# Debugger_Circuit.net
KiCad netlist of a schematic drawn in Altium Designer
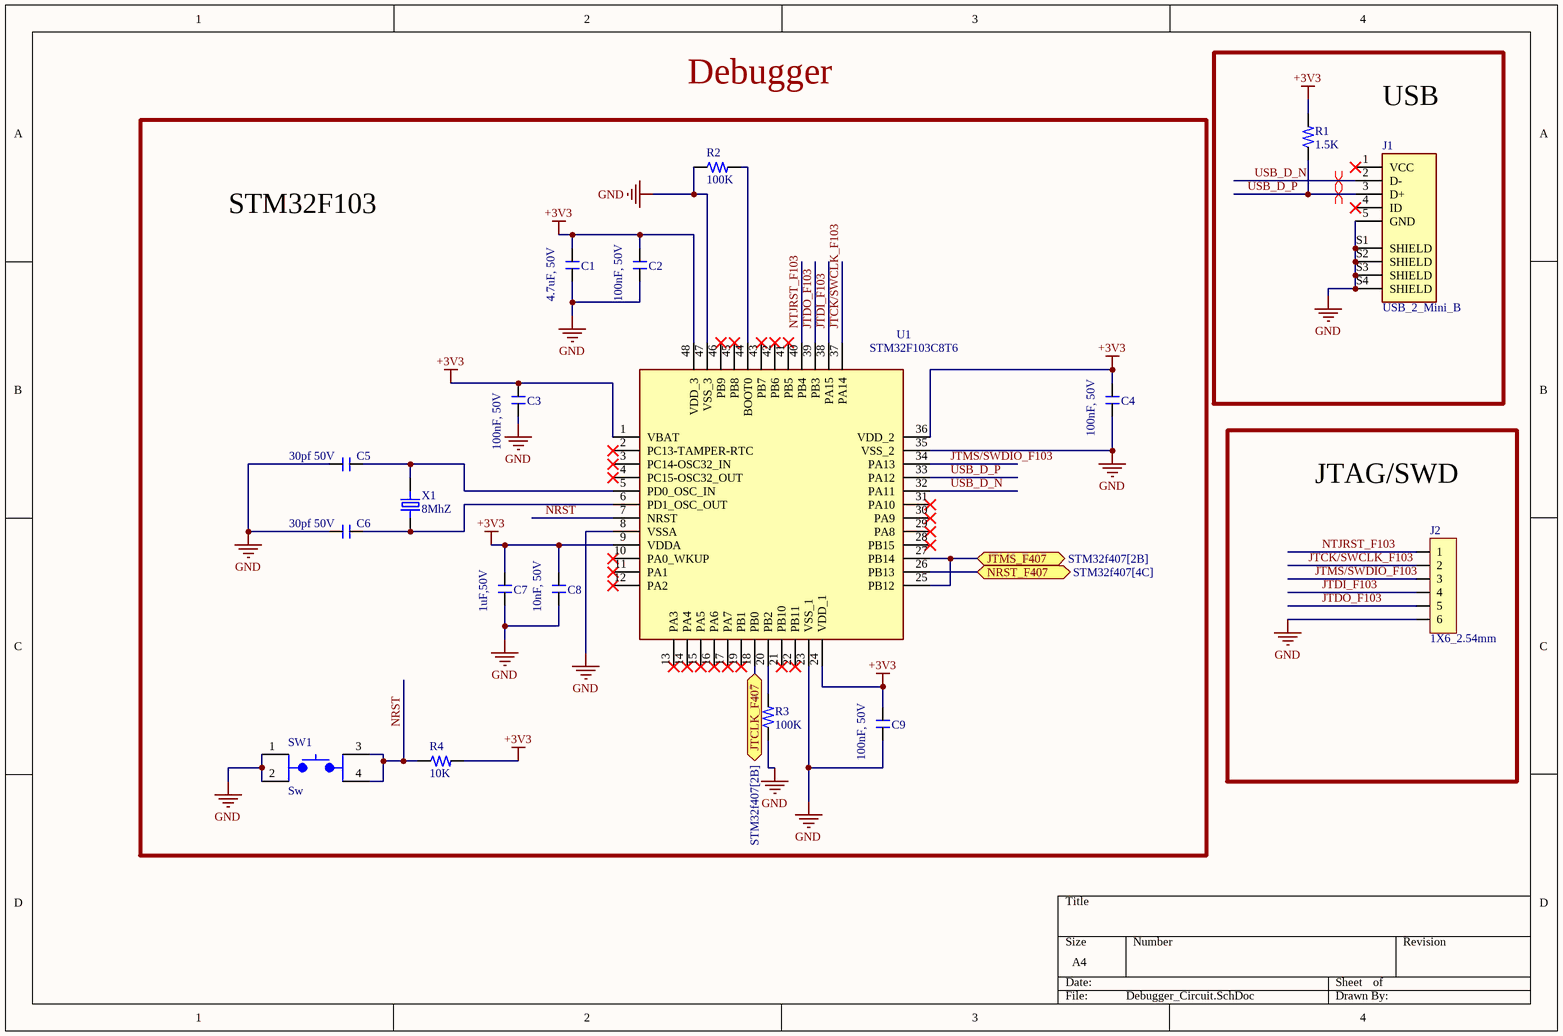
[diagram p0: Debugger_Circuit.SchDoc]

(export (version "E")
  (design (tool "Eeschema 10.0.6"))
  (components
    (comp (ref "C1")
      (value "4.7uF, 50V")
      (footprint "Capacitor_0805")
      (description "Multilayer Ceramic Capacitor, 4.7 uF, 50 V, ï¿½ 10%, X5R, 0805 [2012 Metric]")
      (fields
        (field (name "MANUFACTURER") "Murata")
        (field (name "MANUFACTURER PART NUMBER") "GRM21BR61H475KE51L")
      )
      (libsource (lib "Schematics_Library_Hanif") (part "Cap_4.7uF_0805"))
    )
    (comp (ref "C2")
      (value "100nF, 50V")
      (footprint "Capacitor_0805")
      (description "Multilayer Ceramic Capacitor, 0.1 uF, 50 V, ï¿½ 10%, X7R, 0805 [2012 Metric]")
      (fields
        (field (name "MANUFACTURER") "Samsung")
        (field (name "MANUFACTURER PART NUMBER") "CL21B104KBCNNNC")
      )
      (libsource (lib "Schematics_Library_Hanif") (part "Cap_100nF_0805"))
    )
    (comp (ref "C3")
      (value "100nF, 50V")
      (footprint "Capacitor_0805")
      (description "Multilayer Ceramic Capacitor, 0.1 uF, 50 V, ï¿½ 10%, X7R, 0805 [2012 Metric]")
      (fields
        (field (name "MANUFACTURER") "Samsung")
        (field (name "MANUFACTURER PART NUMBER") "CL21B104KBCNNNC")
      )
      (libsource (lib "Schematics_Library_Hanif") (part "Cap_100nF_0805"))
    )
    (comp (ref "C4")
      (value "100nF, 50V")
      (footprint "Capacitor_0805")
      (description "Multilayer Ceramic Capacitor, 0.1 uF, 50 V, ï¿½ 10%, X7R, 0805 [2012 Metric]")
      (fields
        (field (name "MANUFACTURER") "Samsung")
        (field (name "MANUFACTURER PART NUMBER") "CL21B104KBCNNNC")
      )
      (libsource (lib "Schematics_Library_Hanif") (part "Cap_100nF_0805"))
    )
    (comp (ref "C5")
      (value "30pf 50V")
      (footprint "Capacitor_0805")
      (fields
        (field (name "MANUFACTURER") "KEMET")
        (field (name "MANUFACTURER PART NUMBER") "C0805C300K5GACTU")
      )
      (libsource (lib "Schematics_Library_Hanif") (part "Cap_30pf_0805"))
    )
    (comp (ref "C6")
      (value "30pf 50V")
      (footprint "Capacitor_0805")
      (fields
        (field (name "MANUFACTURER") "KEMET")
        (field (name "MANUFACTURER PART NUMBER") "C0805C300K5GACTU")
      )
      (libsource (lib "Schematics_Library_Hanif") (part "Cap_30pf_0805"))
    )
    (comp (ref "C7")
      (value "1uF,50V")
      (footprint "Capacitor_0805")
      (description "0805 1 uF 50 V ±5 % Tolerance X7R Surface Mount Multilayer Ceramic Capacitor")
      (fields
        (field (name "MANUFACTURER") "Yageo")
        (field (name "MANUFACTURER PART NUMBER") "CC0805JKX7R9BB105")
      )
      (libsource (lib "Schematics_Library_Hanif") (part "Cap_1uF_0805"))
    )
    (comp (ref "C8")
      (value "10nF, 50V")
      (footprint "Capacitor_0805")
      (description "Multilayer Ceramic Capacitors MLCC - SMD/SMT 50V 0.01uF X7R 0805 10% AEC-Q200")
      (fields
        (field (name "MANUFACTURER") "KEMET")
        (field (name "MANUFACTURER PART NUMBER") "C0805C103K5RECAUTO")
      )
      (libsource (lib "Schematics_Library_Hanif") (part "Cap_10nF_0805"))
    )
    (comp (ref "C9")
      (value "100nF, 50V")
      (footprint "Capacitor_0805")
      (description "Multilayer Ceramic Capacitor, 0.1 uF, 50 V, ï¿½ 10%, X7R, 0805 [2012 Metric]")
      (fields
        (field (name "MANUFACTURER") "Samsung")
        (field (name "MANUFACTURER PART NUMBER") "CL21B104KBCNNNC")
      )
      (libsource (lib "Schematics_Library_Hanif") (part "Cap_100nF_0805"))
    )
    (comp (ref "J1")
      (value "USB_2_Mini_B")
      (footprint "USB_2_Mini")
      (description "Conn Mini USB 2.0 Type B RCP 5 POS 0.8mm Solder RA SMD 5 Terminal 1 Port")
      (fields
        (field (name "MANUFACTURER") "EDAC")
        (field (name "MANUFACTURER PART NUMBER") "690-005-299-043")
      )
      (libsource (lib "Schematics_Library_Hanif") (part "USB2_Mini_690-B_005-299-043"))
    )
    (comp (ref "J2")
      (value "1X6_2.54mm")
      (footprint "Header_1X6_2.54mm")
      (description "KK 254 Wire-to-Board Header Single Row Vertical 6 Circuits PA Polyamide Nylon Gold Plating")
      (fields (field (name "MANUFACTURER") "Molex") (field (name "MANUFACTURER PART NUMBER") "22-10-2061"))
      (libsource (lib "Schematics_Library_Hanif") (part "Header_Male_1X6_2.54mm"))
    )
    (comp (ref "R1")
      (value "1.5K")
      (footprint "Resistor_0805")
      (description "Res Thick Film 0805 1.5K Ohm 1% 0.125W(1/8W) ±100ppm/C Pad SMD T/R")
      (fields
        (field (name "MANUFACTURER") "TE Connectivity")
        (field (name "MANUFACTURER PART NUMBER") "CRG0805F1K5")
      )
      (libsource (lib "Schematics_Library_Hanif") (part "Res_1.5K0805"))
    )
    (comp (ref "R2")
      (value "100K")
      (footprint "Resistor_0603")
      (description "Res Thick Film 0603 100K Ohm 1% 0.1W(1/10W) ±100ppm/C Pad SMD Automotive T/R")
      (fields
        (field (name "MANUFACTURER") "Stackpole Electronics")
        (field (name "MANUFACTURER PART NUMBER") "RMCF0603FT100K")
      )
      (libsource (lib "Schematics_Library_Hanif") (part "R_100K_0603"))
    )
    (comp (ref "R3")
      (value "100K")
      (footprint "Resistor_0603")
      (description "Res Thick Film 0603 100K Ohm 1% 0.1W(1/10W) ±100ppm/C Pad SMD Automotive T/R")
      (fields
        (field (name "MANUFACTURER") "Stackpole Electronics")
        (field (name "MANUFACTURER PART NUMBER") "RMCF0603FT100K")
      )
      (libsource (lib "Schematics_Library_Hanif") (part "R_100K_0603"))
    )
    (comp (ref "R4")
      (value "10K")
      (footprint "Resistor_0603")
      (description "SMD Chip Resistor, 10 kOhm, ï¿½ 1%, 100 mW, 0603 [1608 Metric], Thick Film, General Purpose")
      (fields
        (field (name "MANUFACTURER") "Yageo")
        (field (name "MANUFACTURER PART NUMBER") "RC0603FR-0710KL")
      )
      (libsource (lib "Schematics_Library_Hanif") (part "R_10K_0603"))
    )
    (comp (ref "SW1")
      (value "Sw")
      (footprint "SW_Tactile_SMD")
      (description "TL3305A Series SPST 12 V 4.5 x 4.5 mm 260 gf Top Actuated SMT Tactile Switch")
      (fields
        (field (name "MANUFACTURER") "E-Switch")
        (field (name "MANUFACTURER PART NUMBER") "TL3305AF260QG")
      )
      (libsource (lib "Schematics_Library_Hanif") (part "SW_Tactile_SPST"))
    )
    (comp (ref "U1")
      (value "STM32F103C8T6")
      (footprint "48-LQFP")
      (description "ARM Cortex-M3 STM32 F1 Microcontroller 32-Bit 72MHz 64kB FLASH LQFP48 STM32F103C8T6")
      (fields (field (name "MANUFACTURER") "STMicroelectronics"))
      (libsource (lib "Schematics_Library_Hanif") (part "MCU_STM32F103C8T6"))
    )
    (comp (ref "X1")
      (value "8MhZ")
      (footprint "XTAL_8MhZ")
      (description "Crystal 8MHz ±30ppm (Tol) ±50ppm (Stability) 32pF FUND 60Ohm 2-Pin HC-49/USX SMD T/R")
      (fields
        (field (name "MANUFACTURER") "ECS International")
        (field (name "MANUFACTURER PART NUMBER") "ECS-80-32-5PX-TR")
      )
      (libsource (lib "Schematics_Library_Hanif") (part "Xtal_8MHz"))
    )
  )
  (nets
    (net (code "1") (name "+3V3") (class "Default")
      (node (ref "C1") (pin "1") (pinfunction "1_1") (pintype "passive"))
      (node (ref "C2") (pin "2") (pinfunction "2_2") (pintype "passive"))
      (node (ref "C3") (pin "2") (pinfunction "2_2") (pintype "passive"))
      (node (ref "C4") (pin "2") (pinfunction "2_2") (pintype "passive"))
      (node (ref "C7") (pin "2") (pinfunction "2_2") (pintype "passive"))
      (node (ref "C8") (pin "2") (pinfunction "2_2") (pintype "passive"))
      (node (ref "C9") (pin "2") (pinfunction "2_2") (pintype "passive"))
      (node (ref "R1") (pin "2") (pinfunction "2_2") (pintype "passive"))
      (node (ref "R4") (pin "2") (pinfunction "2_2") (pintype "passive"))
      (node (ref "U1") (pin "1") (pinfunction "VBAT_1") (pintype "passive"))
      (node (ref "U1") (pin "24") (pinfunction "VDD_1_24") (pintype "passive"))
      (node (ref "U1") (pin "36") (pinfunction "VDD_2_36") (pintype "passive"))
      (node (ref "U1") (pin "48") (pinfunction "VDD_3_48") (pintype "passive"))
      (node (ref "U1") (pin "9") (pinfunction "VDDA_9") (pintype "passive"))
    )
    (net (code "2") (name "/JTCK{slash}SWCLK_F103") (class "Default")
      (node (ref "J2") (pin "2") (pinfunction "2_2") (pintype "passive"))
      (node (ref "U1") (pin "37") (pinfunction "PA14_37") (pintype "passive"))
    )
    (net (code "3") (name "/JTCLK_F407") (class "Default")
      (node (ref "U1") (pin "18") (pinfunction "PB0_18") (pintype "passive"))
    )
    (net (code "4") (name "/JTDI_F103") (class "Default")
      (node (ref "J2") (pin "4") (pinfunction "4_4") (pintype "passive"))
      (node (ref "U1") (pin "38") (pinfunction "PA15_38") (pintype "passive"))
    )
    (net (code "5") (name "/JTDO_F103") (class "Default")
      (node (ref "J2") (pin "5") (pinfunction "5_5") (pintype "passive"))
      (node (ref "U1") (pin "39") (pinfunction "PB3_39") (pintype "passive"))
    )
    (net (code "6") (name "/JTMS_F407") (class "Default")
      (node (ref "U1") (pin "25") (pinfunction "PB12_25") (pintype "passive"))
      (node (ref "U1") (pin "27") (pinfunction "PB14_27") (pintype "passive"))
    )
    (net (code "7") (name "/JTMS{slash}SWDIO_F103") (class "Default")
      (node (ref "J2") (pin "3") (pinfunction "3_3") (pintype "passive"))
      (node (ref "U1") (pin "34") (pinfunction "PA13_34") (pintype "passive"))
    )
    (net (code "8") (name "/NRST") (class "Default")
      (node (ref "R4") (pin "1") (pinfunction "1_1") (pintype "passive"))
      (node (ref "SW1") (pin "3") (pinfunction "3_3") (pintype "passive"))
      (node (ref "SW1") (pin "4") (pinfunction "4_4") (pintype "passive"))
      (node (ref "U1") (pin "7") (pinfunction "NRST_7") (pintype "passive"))
    )
    (net (code "9") (name "/NRST_F407") (class "Default")
      (node (ref "U1") (pin "26") (pinfunction "PB13_26") (pintype "passive"))
    )
    (net (code "10") (name "/NTJRST_F103") (class "Default")
      (node (ref "J2") (pin "1") (pinfunction "1_1") (pintype "passive"))
      (node (ref "U1") (pin "40") (pinfunction "PB4_40") (pintype "passive"))
    )
    (net (code "11") (name "/USB_D_N") (class "Default")
      (node (ref "J1") (pin "2") (pinfunction "D-_2") (pintype "passive"))
      (node (ref "U1") (pin "32") (pinfunction "PA11_32") (pintype "passive"))
    )
    (net (code "12") (name "/USB_D_P") (class "Default")
      (node (ref "J1") (pin "3") (pinfunction "D+_3") (pintype "passive"))
      (node (ref "R1") (pin "1") (pinfunction "1_1") (pintype "passive"))
      (node (ref "U1") (pin "33") (pinfunction "PA12_33") (pintype "passive"))
    )
    (net (code "13") (name "GND") (class "Default")
      (node (ref "C1") (pin "2") (pinfunction "2_2") (pintype "passive"))
      (node (ref "C2") (pin "1") (pinfunction "1_1") (pintype "passive"))
      (node (ref "C3") (pin "1") (pinfunction "1_1") (pintype "passive"))
      (node (ref "C4") (pin "1") (pinfunction "1_1") (pintype "passive"))
      (node (ref "C5") (pin "1") (pinfunction "1_1") (pintype "passive"))
      (node (ref "C6") (pin "1") (pinfunction "1_1") (pintype "passive"))
      (node (ref "C7") (pin "1") (pinfunction "1_1") (pintype "passive"))
      (node (ref "C8") (pin "1") (pinfunction "1_1") (pintype "passive"))
      (node (ref "C9") (pin "1") (pinfunction "1_1") (pintype "passive"))
      (node (ref "J1") (pin "5") (pinfunction "GND_5") (pintype "passive"))
      (node (ref "J1") (pin "S1") (pinfunction "SHIELD_S1") (pintype "passive"))
      (node (ref "J1") (pin "S2") (pinfunction "SHIELD_S2") (pintype "passive"))
      (node (ref "J1") (pin "S3") (pinfunction "SHIELD_S3") (pintype "passive"))
      (node (ref "J1") (pin "S4") (pinfunction "SHIELD_S4") (pintype "passive"))
      (node (ref "J2") (pin "6") (pinfunction "6_6") (pintype "passive"))
      (node (ref "R2") (pin "1") (pinfunction "1_1") (pintype "passive"))
      (node (ref "R3") (pin "1") (pinfunction "1_1") (pintype "passive"))
      (node (ref "SW1") (pin "1") (pinfunction "1_1") (pintype "passive"))
      (node (ref "SW1") (pin "2") (pinfunction "2_2") (pintype "passive"))
      (node (ref "U1") (pin "23") (pinfunction "VSS_1_23") (pintype "passive"))
      (node (ref "U1") (pin "35") (pinfunction "VSS_2_35") (pintype "passive"))
      (node (ref "U1") (pin "47") (pinfunction "VSS_3_47") (pintype "passive"))
      (node (ref "U1") (pin "8") (pinfunction "VSSA_8") (pintype "passive"))
    )
    (net (code "14") (name "Net-(U1-BOOT0)") (class "Default")
      (node (ref "R2") (pin "2") (pinfunction "2_2") (pintype "passive"))
      (node (ref "U1") (pin "44") (pinfunction "BOOT0_44") (pintype "passive"))
    )
    (net (code "15") (name "Net-(U1-PB2)") (class "Default")
      (node (ref "R3") (pin "2") (pinfunction "2_2") (pintype "passive"))
      (node (ref "U1") (pin "20") (pinfunction "PB2_20") (pintype "passive"))
    )
    (net (code "16") (name "Net-(U1-PD0_OSC_IN)") (class "Default")
      (node (ref "C5") (pin "2") (pinfunction "2_2") (pintype "passive"))
      (node (ref "U1") (pin "5") (pinfunction "PD0_OSC_IN_5") (pintype "passive"))
      (node (ref "X1") (pin "2") (pinfunction "2_2") (pintype "passive"))
    )
    (net (code "17") (name "Net-(U1-PD1_OSC_OUT)") (class "Default")
      (node (ref "C6") (pin "2") (pinfunction "2_2") (pintype "passive"))
      (node (ref "U1") (pin "6") (pinfunction "PD1_OSC_OUT_6") (pintype "passive"))
      (node (ref "X1") (pin "1") (pinfunction "1_1") (pintype "passive"))
    )
    (net (code "18") (name "unconnected-(J1-ID-Pad4)") (class "Default")
      (node (ref "J1") (pin "4") (pinfunction "ID_4") (pintype "passive+no_connect"))
    )
    (net (code "19") (name "unconnected-(J1-VCC-Pad1)") (class "Default")
      (node (ref "J1") (pin "1") (pinfunction "VCC_1") (pintype "passive+no_connect"))
    )
    (net (code "20") (name "unconnected-(U1-PA0_WKUP-Pad10)") (class "Default")
      (node (ref "U1") (pin "10") (pinfunction "PA0_WKUP_10") (pintype "passive+no_connect"))
    )
    (net (code "21") (name "unconnected-(U1-PA1-Pad11)") (class "Default")
      (node (ref "U1") (pin "11") (pinfunction "PA1_11") (pintype "passive+no_connect"))
    )
    (net (code "22") (name "unconnected-(U1-PA2-Pad12)") (class "Default")
      (node (ref "U1") (pin "12") (pinfunction "PA2_12") (pintype "passive+no_connect"))
    )
    (net (code "23") (name "unconnected-(U1-PA3-Pad13)") (class "Default")
      (node (ref "U1") (pin "13") (pinfunction "PA3_13") (pintype "passive+no_connect"))
    )
    (net (code "24") (name "unconnected-(U1-PA4-Pad14)") (class "Default")
      (node (ref "U1") (pin "14") (pinfunction "PA4_14") (pintype "passive+no_connect"))
    )
    (net (code "25") (name "unconnected-(U1-PA5-Pad15)") (class "Default")
      (node (ref "U1") (pin "15") (pinfunction "PA5_15") (pintype "passive+no_connect"))
    )
    (net (code "26") (name "unconnected-(U1-PA6-Pad16)") (class "Default")
      (node (ref "U1") (pin "16") (pinfunction "PA6_16") (pintype "passive+no_connect"))
    )
    (net (code "27") (name "unconnected-(U1-PA7-Pad17)") (class "Default")
      (node (ref "U1") (pin "17") (pinfunction "PA7_17") (pintype "passive+no_connect"))
    )
    (net (code "28") (name "unconnected-(U1-PA8-Pad29)") (class "Default")
      (node (ref "U1") (pin "29") (pinfunction "PA8_29") (pintype "passive+no_connect"))
    )
    (net (code "29") (name "unconnected-(U1-PA9-Pad30)") (class "Default")
      (node (ref "U1") (pin "30") (pinfunction "PA9_30") (pintype "passive+no_connect"))
    )
    (net (code "30") (name "unconnected-(U1-PA10-Pad31)") (class "Default")
      (node (ref "U1") (pin "31") (pinfunction "PA10_31") (pintype "passive+no_connect"))
    )
    (net (code "31") (name "unconnected-(U1-PB1-Pad19)") (class "Default")
      (node (ref "U1") (pin "19") (pinfunction "PB1_19") (pintype "passive+no_connect"))
    )
    (net (code "32") (name "unconnected-(U1-PB5-Pad41)") (class "Default")
      (node (ref "U1") (pin "41") (pinfunction "PB5_41") (pintype "passive+no_connect"))
    )
    (net (code "33") (name "unconnected-(U1-PB6-Pad42)") (class "Default")
      (node (ref "U1") (pin "42") (pinfunction "PB6_42") (pintype "passive+no_connect"))
    )
    (net (code "34") (name "unconnected-(U1-PB7-Pad43)") (class "Default")
      (node (ref "U1") (pin "43") (pinfunction "PB7_43") (pintype "passive+no_connect"))
    )
    (net (code "35") (name "unconnected-(U1-PB8-Pad45)") (class "Default")
      (node (ref "U1") (pin "45") (pinfunction "PB8_45") (pintype "passive+no_connect"))
    )
    (net (code "36") (name "unconnected-(U1-PB9-Pad46)") (class "Default")
      (node (ref "U1") (pin "46") (pinfunction "PB9_46") (pintype "passive+no_connect"))
    )
    (net (code "37") (name "unconnected-(U1-PB10-Pad21)") (class "Default")
      (node (ref "U1") (pin "21") (pinfunction "PB10_21") (pintype "passive+no_connect"))
    )
    (net (code "38") (name "unconnected-(U1-PB11-Pad22)") (class "Default")
      (node (ref "U1") (pin "22") (pinfunction "PB11_22") (pintype "passive+no_connect"))
    )
    (net (code "39") (name "unconnected-(U1-PB15-Pad28)") (class "Default")
      (node (ref "U1") (pin "28") (pinfunction "PB15_28") (pintype "passive+no_connect"))
    )
    (net (code "40") (name "unconnected-(U1-PC13-TAMPER-RTC-Pad2)") (class "Default")
      (node (ref "U1") (pin "2") (pinfunction "PC13-TAMPER-RTC_2") (pintype "passive+no_connect"))
    )
    (net (code "41") (name "unconnected-(U1-PC14-OSC32_IN-Pad3)") (class "Default")
      (node (ref "U1") (pin "3") (pinfunction "PC14-OSC32_IN_3") (pintype "passive+no_connect"))
    )
    (net (code "42") (name "unconnected-(U1-PC15-OSC32_OUT-Pad4)") (class "Default")
      (node (ref "U1") (pin "4") (pinfunction "PC15-OSC32_OUT_4") (pintype "passive+no_connect"))
    )
  )
)
